# Grove_-_PIR_motion_sensor_v1_1b.net
KiCad netlist of a schematic drawn in EAGLE
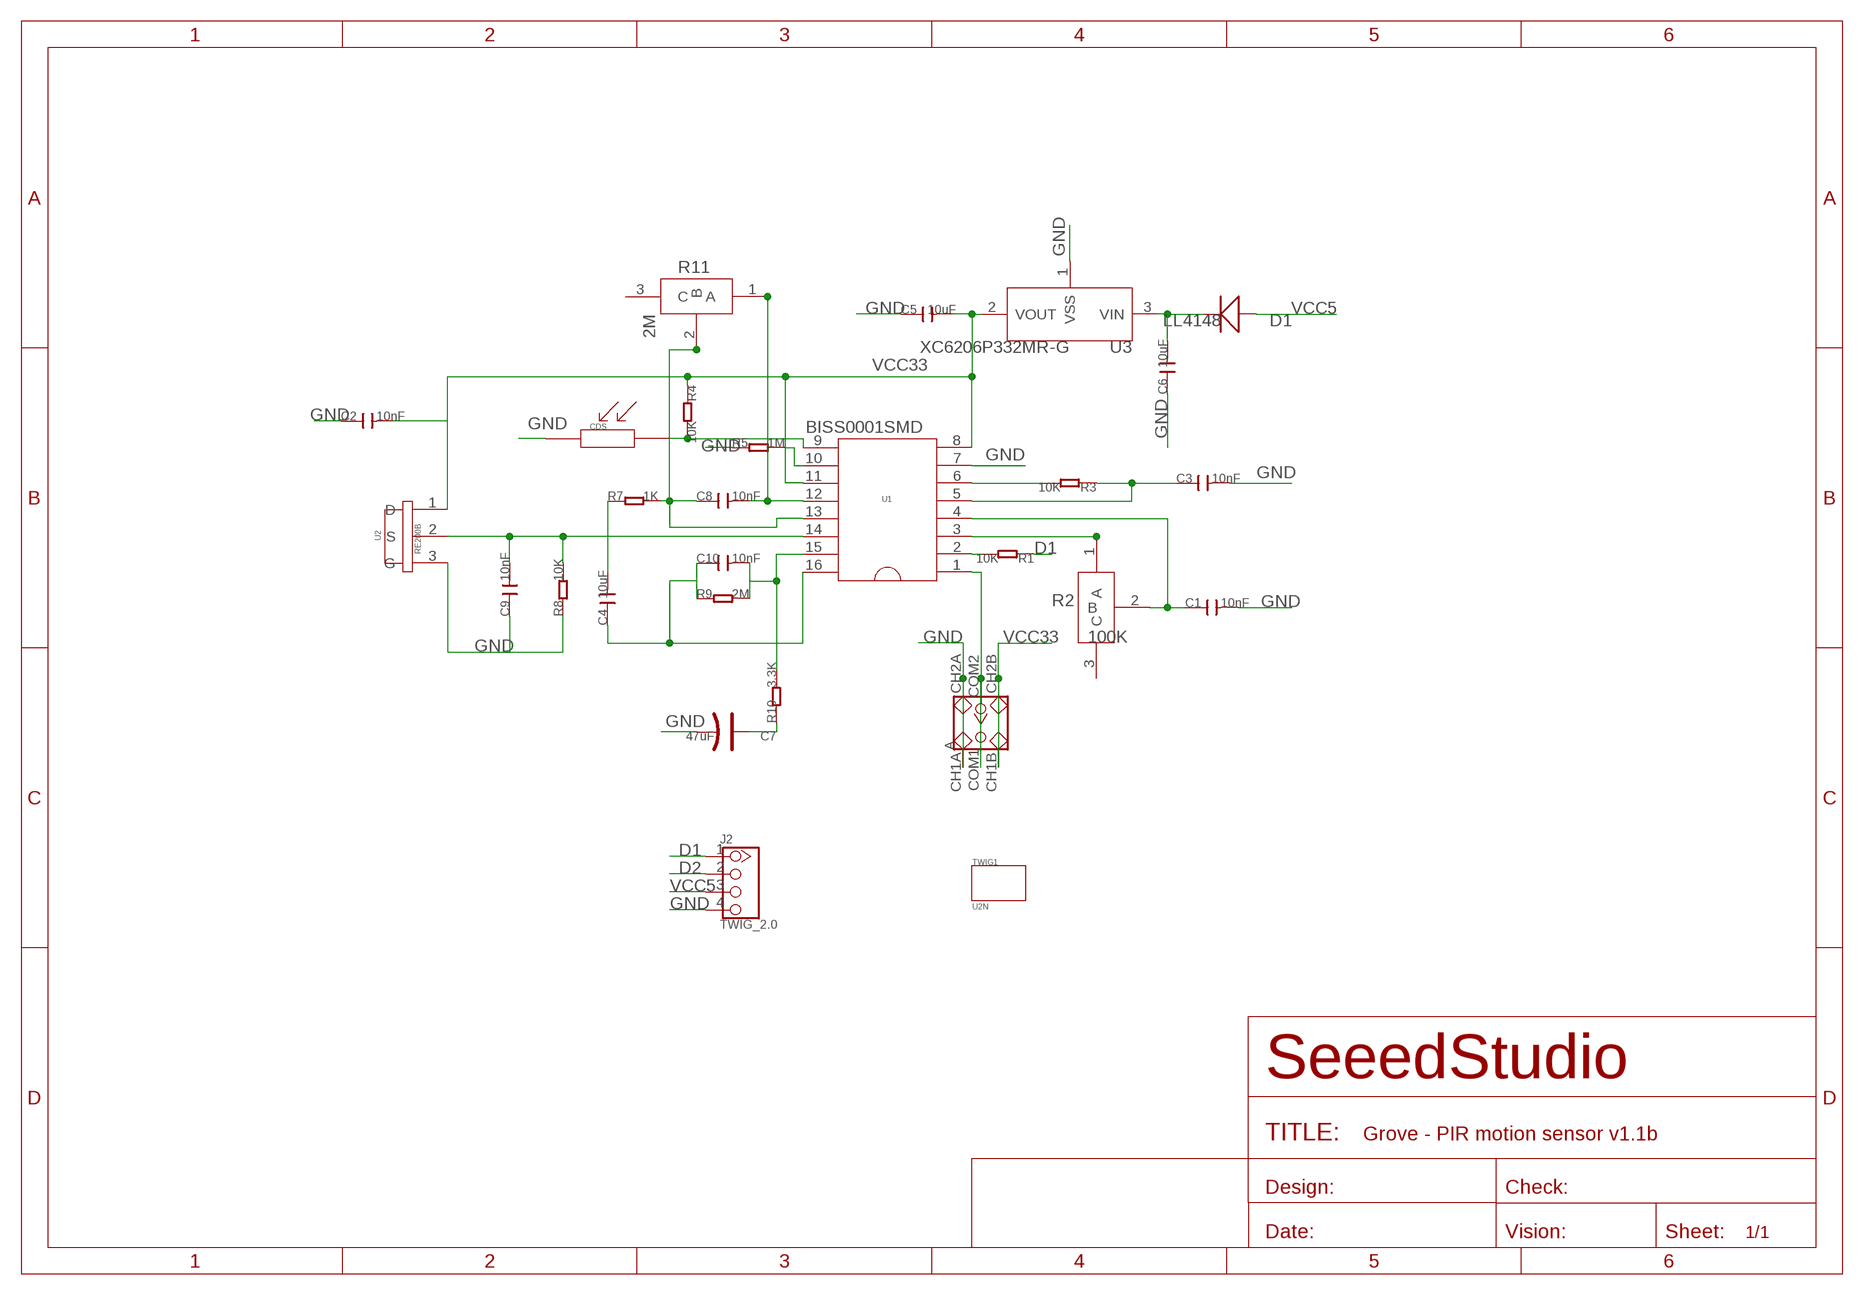
[diagram p0: schematic, sheet 1]

(export (version "E")
  (design (tool "Eeschema 10.0.6"))
  (components
    (comp (ref "A")
      (value "SWITCH-2CH-6P")
      (footprint "eagle-import:6P-2CH-2.54-7.6X3.0")
      (libsource (lib "eagle-import") (part "SWITCH-2CH-6P"))
    )
    (comp (ref "C1")
      (value "10nF")
      (footprint "eagle-import:C0603")
      (libsource (lib "eagle-import") (part "C-0603"))
    )
    (comp (ref "C2")
      (value "10nF")
      (footprint "eagle-import:C0603")
      (libsource (lib "eagle-import") (part "C-0603"))
    )
    (comp (ref "C3")
      (value "10nF")
      (footprint "eagle-import:C0603")
      (libsource (lib "eagle-import") (part "C-0603"))
    )
    (comp (ref "C4")
      (value "10uF")
      (footprint "eagle-import:C0805")
      (libsource (lib "eagle-import") (part "C-0805"))
    )
    (comp (ref "C5")
      (value "10uF")
      (footprint "eagle-import:C0805")
      (libsource (lib "eagle-import") (part "C-0805"))
    )
    (comp (ref "C6")
      (value "10uF")
      (footprint "eagle-import:C0805")
      (libsource (lib "eagle-import") (part "C-0805"))
    )
    (comp (ref "C7")
      (value "47uF")
      (footprint "eagle-import:AVX-B")
      (libsource (lib "eagle-import") (part "CAP-AVX-B"))
    )
    (comp (ref "C8")
      (value "10nF")
      (footprint "eagle-import:C0603")
      (libsource (lib "eagle-import") (part "C-0603"))
    )
    (comp (ref "C9")
      (value "10nF")
      (footprint "eagle-import:C0603")
      (libsource (lib "eagle-import") (part "C-0603"))
    )
    (comp (ref "C10")
      (value "10nF")
      (footprint "eagle-import:C0603")
      (libsource (lib "eagle-import") (part "C-0603"))
    )
    (comp (ref "CDS")
      (value "CDS")
      (footprint "eagle-import:CDS")
      (libsource (lib "eagle-import") (part "CDS"))
    )
    (comp (ref "D1")
      (value "LL4148")
      (footprint "eagle-import:SOD123")
      (libsource (lib "eagle-import") (part "D'1206'"))
    )
    (comp (ref "J2")
      (value "TWIG_2.0")
      (footprint "eagle-import:2.0_1X4")
      (libsource (lib "eagle-import") (part "TWIG_2.0"))
    )
    (comp (ref "R1")
      (value "10K")
      (footprint "eagle-import:R0603")
      (libsource (lib "eagle-import") (part "R-0603"))
    )
    (comp (ref "R2")
      (value "100K")
      (footprint "eagle-import:R_REG")
      (libsource (lib "eagle-import") (part "R_REG"))
    )
    (comp (ref "R3")
      (value "10K")
      (footprint "eagle-import:R0603")
      (libsource (lib "eagle-import") (part "R-0603"))
    )
    (comp (ref "R4")
      (value "10K")
      (footprint "eagle-import:R0603")
      (libsource (lib "eagle-import") (part "R-0603"))
    )
    (comp (ref "R5")
      (value "1M")
      (footprint "eagle-import:R0603")
      (libsource (lib "eagle-import") (part "R-0603"))
    )
    (comp (ref "R7")
      (value "1K")
      (footprint "eagle-import:R0603")
      (libsource (lib "eagle-import") (part "R-0603"))
    )
    (comp (ref "R8")
      (value "10K")
      (footprint "eagle-import:R0603")
      (libsource (lib "eagle-import") (part "R-0603"))
    )
    (comp (ref "R9")
      (value "2M")
      (footprint "eagle-import:R0603")
      (libsource (lib "eagle-import") (part "R-0603"))
    )
    (comp (ref "R10")
      (value "3.3K")
      (footprint "eagle-import:R0603")
      (libsource (lib "eagle-import") (part "R-0603"))
    )
    (comp (ref "R11")
      (value "2M")
      (footprint "eagle-import:R_REG")
      (libsource (lib "eagle-import") (part "R_REG"))
    )
    (comp (ref "TWIG1")
      (value "U2N")
      (footprint "eagle-import:U2N")
      (libsource (lib "eagle-import") (part "U2N"))
    )
    (comp (ref "U1")
      (value "BISS0001SMD")
      (footprint "eagle-import:SOP16")
      (libsource (lib "eagle-import") (part "BISS0001SMD"))
    )
    (comp (ref "U2")
      (value "RE200B")
      (footprint "eagle-import:RE200B")
      (libsource (lib "eagle-import") (part "RE200B"))
    )
    (comp (ref "U3")
      (value "XC6206P332MR-G")
      (footprint "eagle-import:SOT23")
      (libsource (lib "eagle-import") (part "XC6206MR"))
    )
  )
  (nets
    (net (code "1") (name "/D1") (class "Default")
      (node (ref "J2") (pin "1") (pinfunction "1_1") (pintype "bidirectional"))
      (node (ref "R1") (pin "1") (pinfunction "1_1") (pintype "passive"))
    )
    (net (code "2") (name "/D2") (class "Default")
      (node (ref "J2") (pin "2") (pinfunction "2_2") (pintype "bidirectional"))
    )
    (net (code "3") (name "/GND") (class "Default")
      (node (ref "A") (pin "CH1A") (pinfunction "CH1A_CH1A") (pintype "bidirectional"))
      (node (ref "A") (pin "CH2A") (pinfunction "CH2A_CH2A") (pintype "bidirectional"))
      (node (ref "C1") (pin "2") (pinfunction "2_2") (pintype "passive"))
      (node (ref "C2") (pin "1") (pinfunction "1_1") (pintype "passive"))
      (node (ref "C3") (pin "2") (pinfunction "2_2") (pintype "passive"))
      (node (ref "C5") (pin "1") (pinfunction "1_1") (pintype "passive"))
      (node (ref "C6") (pin "1") (pinfunction "1_1") (pintype "passive"))
      (node (ref "C7") (pin "-") (pinfunction "-_-") (pintype "passive"))
      (node (ref "C9") (pin "1") (pinfunction "1_1") (pintype "passive"))
      (node (ref "CDS") (pin "1") (pinfunction "P$1_1") (pintype "bidirectional"))
      (node (ref "J2") (pin "4") (pinfunction "4_4") (pintype "bidirectional"))
      (node (ref "R5") (pin "1") (pinfunction "1_1") (pintype "passive"))
      (node (ref "R8") (pin "1") (pinfunction "1_1") (pintype "passive"))
      (node (ref "U1") (pin "7") (pinfunction "P$7_7") (pintype "bidirectional"))
      (node (ref "U2") (pin "3") (pinfunction "G_3") (pintype "bidirectional"))
      (node (ref "U3") (pin "1") (pinfunction "VSS_1") (pintype "power_in"))
    )
    (net (code "4") (name "/VCC5") (class "Default")
      (node (ref "D1") (pin "+") (pinfunction "+_+") (pintype "passive"))
      (node (ref "J2") (pin "3") (pinfunction "3_3") (pintype "bidirectional"))
    )
    (net (code "5") (name "/VCC33") (class "Default")
      (node (ref "A") (pin "CH1B") (pinfunction "CH1B_CH1B") (pintype "bidirectional"))
      (node (ref "A") (pin "CH2B") (pinfunction "CH2B_CH2B") (pintype "bidirectional"))
      (node (ref "C2") (pin "2") (pinfunction "2_2") (pintype "passive"))
      (node (ref "C5") (pin "2") (pinfunction "2_2") (pintype "passive"))
      (node (ref "R4") (pin "1") (pinfunction "1_1") (pintype "passive"))
      (node (ref "U1") (pin "11") (pinfunction "P$11_11") (pintype "bidirectional"))
      (node (ref "U1") (pin "8") (pinfunction "P$8_8") (pintype "bidirectional"))
      (node (ref "U2") (pin "1") (pinfunction "D_1") (pintype "bidirectional"))
      (node (ref "U3") (pin "2") (pinfunction "VOUT_2") (pintype "output"))
    )
    (net (code "6") (name "Net-(C4-Pad2)") (class "Default")
      (node (ref "C4") (pin "2") (pinfunction "2_2") (pintype "passive"))
      (node (ref "R7") (pin "1") (pinfunction "1_1") (pintype "passive"))
    )
    (net (code "7") (name "Net-(C7-Pad+)") (class "Default")
      (node (ref "C7") (pin "+") (pinfunction "+_+") (pintype "passive"))
      (node (ref "R10") (pin "1") (pinfunction "1_1") (pintype "passive"))
    )
    (net (code "8") (name "Net-(CDS-P$2)") (class "Default")
      (node (ref "CDS") (pin "2") (pinfunction "P$2_2") (pintype "bidirectional"))
      (node (ref "R4") (pin "2") (pinfunction "2_2") (pintype "passive"))
      (node (ref "U1") (pin "9") (pinfunction "P$9_9") (pintype "bidirectional"))
    )
    (net (code "9") (name "Net-(R2-A)") (class "Default")
      (node (ref "R2") (pin "1") (pinfunction "A_1") (pintype "bidirectional"))
      (node (ref "U1") (pin "3") (pinfunction "P$3_3") (pintype "bidirectional"))
    )
    (net (code "10") (name "Net-(R2-B)") (class "Default")
      (node (ref "C1") (pin "1") (pinfunction "1_1") (pintype "passive"))
      (node (ref "R2") (pin "2") (pinfunction "B_2") (pintype "bidirectional"))
      (node (ref "U1") (pin "4") (pinfunction "P$4_4") (pintype "bidirectional"))
    )
    (net (code "11") (name "Net-(R11-A)") (class "Default")
      (node (ref "C8") (pin "2") (pinfunction "2_2") (pintype "passive"))
      (node (ref "R11") (pin "1") (pinfunction "A_1") (pintype "bidirectional"))
      (node (ref "U1") (pin "12") (pinfunction "P$12_12") (pintype "bidirectional"))
    )
    (net (code "12") (name "Net-(R11-B)") (class "Default")
      (node (ref "C8") (pin "1") (pinfunction "1_1") (pintype "passive"))
      (node (ref "R11") (pin "2") (pinfunction "B_2") (pintype "bidirectional"))
      (node (ref "R7") (pin "2") (pinfunction "2_2") (pintype "passive"))
      (node (ref "U1") (pin "13") (pinfunction "P$13_13") (pintype "bidirectional"))
    )
    (net (code "13") (name "Net-(U1-P$1)") (class "Default")
      (node (ref "A") (pin "COM1") (pinfunction "COM1_COM1") (pintype "bidirectional"))
      (node (ref "A") (pin "COM2") (pinfunction "COM2_COM2") (pintype "bidirectional"))
      (node (ref "U1") (pin "1") (pinfunction "P$1_1") (pintype "bidirectional"))
    )
    (net (code "14") (name "Net-(U1-P$2)") (class "Default")
      (node (ref "R1") (pin "2") (pinfunction "2_2") (pintype "passive"))
      (node (ref "U1") (pin "2") (pinfunction "P$2_2") (pintype "bidirectional"))
    )
    (net (code "15") (name "Net-(U1-P$5)") (class "Default")
      (node (ref "C3") (pin "1") (pinfunction "1_1") (pintype "passive"))
      (node (ref "R3") (pin "1") (pinfunction "1_1") (pintype "passive"))
      (node (ref "U1") (pin "5") (pinfunction "P$5_5") (pintype "bidirectional"))
    )
    (net (code "16") (name "Net-(U1-P$6)") (class "Default")
      (node (ref "R3") (pin "2") (pinfunction "2_2") (pintype "passive"))
      (node (ref "U1") (pin "6") (pinfunction "P$6_6") (pintype "bidirectional"))
    )
    (net (code "17") (name "Net-(U1-P$10)") (class "Default")
      (node (ref "R5") (pin "2") (pinfunction "2_2") (pintype "passive"))
      (node (ref "U1") (pin "10") (pinfunction "P$10_10") (pintype "bidirectional"))
    )
    (net (code "18") (name "Net-(U1-P$14)") (class "Default")
      (node (ref "C9") (pin "2") (pinfunction "2_2") (pintype "passive"))
      (node (ref "R8") (pin "2") (pinfunction "2_2") (pintype "passive"))
      (node (ref "U1") (pin "14") (pinfunction "P$14_14") (pintype "bidirectional"))
      (node (ref "U2") (pin "2") (pinfunction "S_2") (pintype "bidirectional"))
    )
    (net (code "19") (name "Net-(U1-P$15)") (class "Default")
      (node (ref "C10") (pin "2") (pinfunction "2_2") (pintype "passive"))
      (node (ref "R10") (pin "2") (pinfunction "2_2") (pintype "passive"))
      (node (ref "R9") (pin "2") (pinfunction "2_2") (pintype "passive"))
      (node (ref "U1") (pin "15") (pinfunction "P$15_15") (pintype "bidirectional"))
    )
    (net (code "20") (name "Net-(U1-P$16)") (class "Default")
      (node (ref "C10") (pin "1") (pinfunction "1_1") (pintype "passive"))
      (node (ref "C4") (pin "1") (pinfunction "1_1") (pintype "passive"))
      (node (ref "R9") (pin "1") (pinfunction "1_1") (pintype "passive"))
      (node (ref "U1") (pin "16") (pinfunction "P$16_16") (pintype "bidirectional"))
    )
    (net (code "21") (name "Net-(U3-VIN)") (class "Default")
      (node (ref "C6") (pin "2") (pinfunction "2_2") (pintype "passive"))
      (node (ref "D1") (pin "-") (pinfunction "-_-") (pintype "passive"))
      (node (ref "U3") (pin "3") (pinfunction "VIN_3") (pintype "input"))
    )
    (net (code "22") (name "unconnected-(R2-C-Pad3)") (class "Default")
      (node (ref "R2") (pin "3") (pinfunction "C_3") (pintype "bidirectional"))
    )
    (net (code "23") (name "unconnected-(R11-C-Pad3)") (class "Default")
      (node (ref "R11") (pin "3") (pinfunction "C_3") (pintype "bidirectional"))
    )
  )
)
